# Cis_Honcho.net
KiCad netlist of a schematic drawn in EAGLE
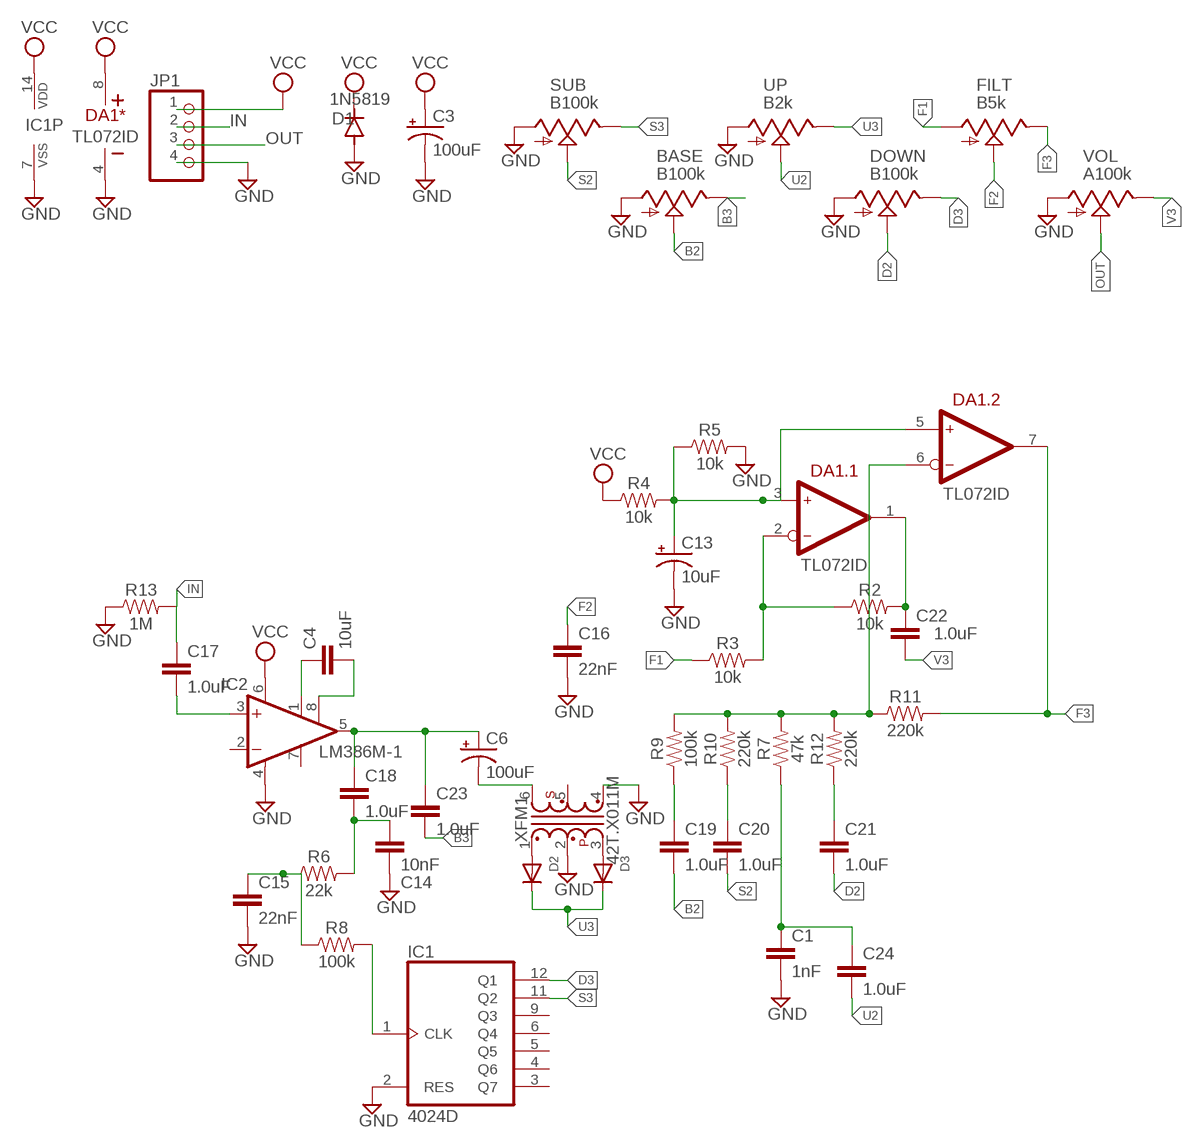
[diagram p0: schematic, sheet 1]

(export (version "E")
  (design (tool "Eeschema 10.0.6"))
  (components
    (comp (ref "BASE")
      (value "B100k")
      (footprint "eagle-import:9MM_SNAP-IN_POT")
      (libsource (lib "eagle-import") (part "9MM_SNAP-IN_POT_"))
    )
    (comp (ref "C1")
      (value "1nF")
      (footprint "eagle-import:0603")
      (libsource (lib "eagle-import") (part "1.0NF/1000PF-0603-50V-10%"))
    )
    (comp (ref "C3")
      (value "100uF")
      (footprint "eagle-import:E2,5-6")
      (libsource (lib "eagle-import") (part "CPOL-USE2.5-6"))
    )
    (comp (ref "C4")
      (value "10uF")
      (footprint "eagle-import:1210")
      (libsource (lib "eagle-import") (part "10UF-1210-50V-20%"))
    )
    (comp (ref "C6")
      (value "100uF")
      (footprint "eagle-import:E2,5-6")
      (libsource (lib "eagle-import") (part "CPOL-USE2.5-6"))
    )
    (comp (ref "C13")
      (value "10uF")
      (footprint "eagle-import:PANASONIC_B")
      (libsource (lib "eagle-import") (part "rcl_334_CPOL-USB"))
    )
    (comp (ref "C14")
      (value "10nF")
      (footprint "eagle-import:0603")
      (libsource (lib "eagle-import") (part "10NF-0603-50V-10%"))
    )
    (comp (ref "C15")
      (value "22nF")
      (footprint "eagle-import:0603")
      (libsource (lib "eagle-import") (part "22NF/22,000PF-0603-50V-10%"))
    )
    (comp (ref "C16")
      (value "22nF")
      (footprint "eagle-import:0603")
      (libsource (lib "eagle-import") (part "22NF/22,000PF-0603-50V-10%"))
    )
    (comp (ref "C17")
      (value "1.0uF")
      (footprint "eagle-import:0603")
      (libsource (lib "eagle-import") (part "1.0UF-0603-16V-10%"))
    )
    (comp (ref "C18")
      (value "1.0uF")
      (footprint "eagle-import:0603")
      (libsource (lib "eagle-import") (part "1.0UF-0603-16V-10%"))
    )
    (comp (ref "C19")
      (value "1.0uF")
      (footprint "eagle-import:0603")
      (libsource (lib "eagle-import") (part "1.0UF-0603-16V-10%"))
    )
    (comp (ref "C20")
      (value "1.0uF")
      (footprint "eagle-import:0603")
      (libsource (lib "eagle-import") (part "1.0UF-0603-16V-10%"))
    )
    (comp (ref "C21")
      (value "1.0uF")
      (footprint "eagle-import:0603")
      (libsource (lib "eagle-import") (part "1.0UF-0603-16V-10%"))
    )
    (comp (ref "C22")
      (value "1.0uF")
      (footprint "eagle-import:0603")
      (libsource (lib "eagle-import") (part "1.0UF-0603-16V-10%"))
    )
    (comp (ref "C23")
      (value "1.0uF")
      (footprint "eagle-import:0603")
      (libsource (lib "eagle-import") (part "1.0UF-0603-16V-10%"))
    )
    (comp (ref "C24")
      (value "1.0uF")
      (footprint "eagle-import:0603")
      (libsource (lib "eagle-import") (part "1.0UF-0603-16V-10%"))
    )
    (comp (ref "D1")
      (value "1N5819")
      (footprint "eagle-import:SOD123")
      (libsource (lib "eagle-import") (part "DIODE-SOD123"))
    )
    (comp (ref "D2")
      (value "DIODESOD-123")
      (footprint "eagle-import:SOD-123")
      (libsource (lib "eagle-import") (part "DIODESOD-123"))
    )
    (comp (ref "D3")
      (value "DIODESOD-123")
      (footprint "eagle-import:SOD-123")
      (libsource (lib "eagle-import") (part "DIODESOD-123"))
    )
    (comp (ref "DA1")
      (value "TL072ID")
      (footprint "eagle-import:SO-8")
      (libsource (lib "eagle-import") (part "TL072ID"))
    )
    (comp (ref "DOWN")
      (value "B100k")
      (footprint "eagle-import:9MM_SNAP-IN_POT")
      (libsource (lib "eagle-import") (part "9MM_SNAP-IN_POT_"))
    )
    (comp (ref "FILT")
      (value "B5k")
      (footprint "eagle-import:9MM_SNAP-IN_POT")
      (libsource (lib "eagle-import") (part "9MM_SNAP-IN_POT_"))
    )
    (comp (ref "IC1")
      (value "4024D")
      (footprint "eagle-import:SO14")
      (libsource (lib "eagle-import") (part "4024D"))
    )
    (comp (ref "IC2")
      (value "LM386M-1")
      (footprint "eagle-import:SO08")
      (libsource (lib "eagle-import") (part "LM386?-M1"))
    )
    (comp (ref "JP1")
      (value "PINHD-1X4")
      (footprint "eagle-import:1X04")
      (libsource (lib "eagle-import") (part "PINHD-1X4"))
    )
    (comp (ref "R2")
      (value "10k")
      (footprint "eagle-import:0603")
      (libsource (lib "eagle-import") (part "10KOHM-0603-1/10W-1%"))
    )
    (comp (ref "R3")
      (value "10k")
      (footprint "eagle-import:0603")
      (libsource (lib "eagle-import") (part "10KOHM-0603-1/10W-1%"))
    )
    (comp (ref "R4")
      (value "10k")
      (footprint "eagle-import:0603")
      (libsource (lib "eagle-import") (part "10KOHM-0603-1/10W-1%"))
    )
    (comp (ref "R5")
      (value "10k")
      (footprint "eagle-import:0603")
      (libsource (lib "eagle-import") (part "10KOHM-0603-1/10W-1%"))
    )
    (comp (ref "R6")
      (value "22k")
      (footprint "eagle-import:0603")
      (libsource (lib "eagle-import") (part "22KOHM-0603-1/10W-1%"))
    )
    (comp (ref "R7")
      (value "47k")
      (footprint "eagle-import:0603")
      (libsource (lib "eagle-import") (part "47KOHM-0603-1/10W-1%"))
    )
    (comp (ref "R8")
      (value "100k")
      (footprint "eagle-import:0603")
      (libsource (lib "eagle-import") (part "100KOHM-0603-1/10W-1%"))
    )
    (comp (ref "R9")
      (value "100k")
      (footprint "eagle-import:0603")
      (libsource (lib "eagle-import") (part "100KOHM-0603-1/10W-1%"))
    )
    (comp (ref "R10")
      (value "220k")
      (footprint "eagle-import:0603")
      (libsource (lib "eagle-import") (part "220KOHM-0603-1/10W-1%"))
    )
    (comp (ref "R11")
      (value "220k")
      (footprint "eagle-import:0603")
      (libsource (lib "eagle-import") (part "220KOHM-0603-1/10W-1%"))
    )
    (comp (ref "R12")
      (value "220k")
      (footprint "eagle-import:0603")
      (libsource (lib "eagle-import") (part "220KOHM-0603-1/10W-1%"))
    )
    (comp (ref "R13")
      (value "1M")
      (footprint "eagle-import:0603")
      (libsource (lib "eagle-import") (part "1MOHM-0603-1/4W-5%"))
    )
    (comp (ref "SUB")
      (value "B100k")
      (footprint "eagle-import:9MM_SNAP-IN_POT")
      (libsource (lib "eagle-import") (part "9MM_SNAP-IN_POT_"))
    )
    (comp (ref "UP")
      (value "B2k")
      (footprint "eagle-import:9MM_SNAP-IN_POT")
      (libsource (lib "eagle-import") (part "9MM_SNAP-IN_POT_"))
    )
    (comp (ref "VOL")
      (value "A100k")
      (footprint "eagle-import:9MM_SNAP-IN_POT")
      (libsource (lib "eagle-import") (part "9MM_SNAP-IN_POT_"))
    )
    (comp (ref "XFM1")
      (value "42T.X011M")
      (footprint "eagle-import:42TM")
      (libsource (lib "eagle-import") (part "42T.XM011"))
    )
  )
  (nets
    (net (code "1") (name "B2") (class "Default")
      (node (ref "BASE") (pin "2") (pinfunction "S_2") (pintype "passive"))
      (node (ref "C19") (pin "2") (pinfunction "2_2") (pintype "passive"))
    )
    (net (code "2") (name "B3") (class "Default")
      (node (ref "BASE") (pin "3") (pinfunction "E_3") (pintype "passive"))
      (node (ref "C23") (pin "2") (pinfunction "2_2") (pintype "passive"))
    )
    (net (code "3") (name "D2") (class "Default")
      (node (ref "C21") (pin "2") (pinfunction "2_2") (pintype "passive"))
      (node (ref "DOWN") (pin "2") (pinfunction "S_2") (pintype "passive"))
    )
    (net (code "4") (name "D3") (class "Default")
      (node (ref "DOWN") (pin "3") (pinfunction "E_3") (pintype "passive"))
      (node (ref "IC1") (pin "12") (pinfunction "Q1_12") (pintype "output"))
    )
    (net (code "5") (name "F1") (class "Default")
      (node (ref "FILT") (pin "1") (pinfunction "A_1") (pintype "passive"))
      (node (ref "R3") (pin "1") (pinfunction "1_1") (pintype "passive"))
    )
    (net (code "6") (name "F2") (class "Default")
      (node (ref "C16") (pin "1") (pinfunction "1_1") (pintype "passive"))
      (node (ref "FILT") (pin "2") (pinfunction "S_2") (pintype "passive"))
    )
    (net (code "7") (name "F3") (class "Default")
      (node (ref "DA1") (pin "7") (pinfunction "OUT_7") (pintype "output"))
      (node (ref "FILT") (pin "3") (pinfunction "E_3") (pintype "passive"))
      (node (ref "R11") (pin "2") (pinfunction "2_2") (pintype "passive"))
    )
    (net (code "8") (name "GND") (class "Default")
      (node (ref "BASE") (pin "1") (pinfunction "A_1") (pintype "passive"))
      (node (ref "C1") (pin "2") (pinfunction "2_2") (pintype "passive"))
      (node (ref "C13") (pin "-") (pinfunction "-_-") (pintype "passive"))
      (node (ref "C14") (pin "2") (pinfunction "2_2") (pintype "passive"))
      (node (ref "C15") (pin "2") (pinfunction "2_2") (pintype "passive"))
      (node (ref "C16") (pin "2") (pinfunction "2_2") (pintype "passive"))
      (node (ref "C3") (pin "-") (pinfunction "-_-") (pintype "passive"))
      (node (ref "D1") (pin "A") (pinfunction "A_A") (pintype "passive"))
      (node (ref "DA1") (pin "4") (pinfunction "V-_4") (pintype "power_in"))
      (node (ref "DOWN") (pin "1") (pinfunction "A_1") (pintype "passive"))
      (node (ref "IC1") (pin "2") (pinfunction "RES_2") (pintype "input"))
      (node (ref "IC1") (pin "7") (pinfunction "VSS_7") (pintype "power_in"))
      (node (ref "IC2") (pin "4") (pinfunction "GND_4") (pintype "power_in"))
      (node (ref "JP1") (pin "4") (pinfunction "4_4") (pintype "passive"))
      (node (ref "R13") (pin "1") (pinfunction "1_1") (pintype "passive"))
      (node (ref "R5") (pin "2") (pinfunction "2_2") (pintype "passive"))
      (node (ref "SUB") (pin "1") (pinfunction "A_1") (pintype "passive"))
      (node (ref "UP") (pin "1") (pinfunction "A_1") (pintype "passive"))
      (node (ref "VOL") (pin "1") (pinfunction "A_1") (pintype "passive"))
      (node (ref "XFM1") (pin "2") (pinfunction "2_2") (pintype "passive"))
      (node (ref "XFM1") (pin "4") (pinfunction "4_4") (pintype "passive"))
    )
    (net (code "9") (name "IN") (class "Default")
      (node (ref "C17") (pin "1") (pinfunction "1_1") (pintype "passive"))
      (node (ref "JP1") (pin "2") (pinfunction "2_2") (pintype "passive"))
      (node (ref "R13") (pin "2") (pinfunction "2_2") (pintype "passive"))
    )
    (net (code "10") (name "Net-(C1-Pad1)") (class "Default")
      (node (ref "C1") (pin "1") (pinfunction "1_1") (pintype "passive"))
      (node (ref "C24") (pin "1") (pinfunction "1_1") (pintype "passive"))
      (node (ref "R7") (pin "1") (pinfunction "1_1") (pintype "passive"))
    )
    (net (code "11") (name "Net-(C4-Pad1)") (class "Default")
      (node (ref "C4") (pin "1") (pinfunction "1_1") (pintype "passive"))
      (node (ref "IC2") (pin "1") (pinfunction "GAIN_1") (pintype "passive"))
    )
    (net (code "12") (name "Net-(C4-Pad2)") (class "Default")
      (node (ref "C4") (pin "2") (pinfunction "2_2") (pintype "passive"))
      (node (ref "IC2") (pin "8") (pinfunction "GAIN_8") (pintype "passive"))
    )
    (net (code "13") (name "Net-(C6-Pad-)") (class "Default")
      (node (ref "C6") (pin "-") (pinfunction "-_-") (pintype "passive"))
      (node (ref "XFM1") (pin "6") (pinfunction "6_6") (pintype "passive"))
    )
    (net (code "14") (name "Net-(C14-Pad1)") (class "Default")
      (node (ref "C14") (pin "1") (pinfunction "1_1") (pintype "passive"))
      (node (ref "C18") (pin "2") (pinfunction "2_2") (pintype "passive"))
      (node (ref "R6") (pin "2") (pinfunction "2_2") (pintype "passive"))
    )
    (net (code "15") (name "Net-(C15-Pad1)") (class "Default")
      (node (ref "C15") (pin "1") (pinfunction "1_1") (pintype "passive"))
      (node (ref "R6") (pin "1") (pinfunction "1_1") (pintype "passive"))
      (node (ref "R8") (pin "1") (pinfunction "1_1") (pintype "passive"))
    )
    (net (code "16") (name "Net-(C19-Pad1)") (class "Default")
      (node (ref "C19") (pin "1") (pinfunction "1_1") (pintype "passive"))
      (node (ref "R9") (pin "1") (pinfunction "1_1") (pintype "passive"))
    )
    (net (code "17") (name "Net-(C20-Pad1)") (class "Default")
      (node (ref "C20") (pin "1") (pinfunction "1_1") (pintype "passive"))
      (node (ref "R10") (pin "1") (pinfunction "1_1") (pintype "passive"))
    )
    (net (code "18") (name "Net-(C21-Pad1)") (class "Default")
      (node (ref "C21") (pin "1") (pinfunction "1_1") (pintype "passive"))
      (node (ref "R12") (pin "1") (pinfunction "1_1") (pintype "passive"))
    )
    (net (code "19") (name "Net-(D2-PadA)") (class "Default")
      (node (ref "D2") (pin "A") (pinfunction "A_A") (pintype "passive"))
      (node (ref "XFM1") (pin "1") (pinfunction "1_1") (pintype "passive"))
    )
    (net (code "20") (name "Net-(D3-PadA)") (class "Default")
      (node (ref "D3") (pin "A") (pinfunction "A_A") (pintype "passive"))
      (node (ref "XFM1") (pin "3") (pinfunction "3_3") (pintype "passive"))
    )
    (net (code "21") (name "Net-(DA1B-IN+)") (class "Default")
      (node (ref "C13") (pin "+") (pinfunction "+_+") (pintype "passive"))
      (node (ref "DA1") (pin "3") (pinfunction "IN+_3") (pintype "input"))
      (node (ref "DA1") (pin "5") (pinfunction "IN+_5") (pintype "input"))
      (node (ref "R4") (pin "2") (pinfunction "2_2") (pintype "passive"))
      (node (ref "R5") (pin "1") (pinfunction "1_1") (pintype "passive"))
    )
    (net (code "22") (name "Net-(DA1B-IN-)") (class "Default")
      (node (ref "DA1") (pin "2") (pinfunction "IN-_2") (pintype "input"))
      (node (ref "R2") (pin "1") (pinfunction "1_1") (pintype "passive"))
      (node (ref "R3") (pin "2") (pinfunction "2_2") (pintype "passive"))
    )
    (net (code "23") (name "Net-(DA1B-OUT)") (class "Default")
      (node (ref "C22") (pin "1") (pinfunction "1_1") (pintype "passive"))
      (node (ref "DA1") (pin "1") (pinfunction "OUT_1") (pintype "output"))
      (node (ref "R2") (pin "2") (pinfunction "2_2") (pintype "passive"))
    )
    (net (code "24") (name "Net-(DA1C-IN-)") (class "Default")
      (node (ref "DA1") (pin "6") (pinfunction "IN-_6") (pintype "input"))
      (node (ref "R10") (pin "2") (pinfunction "2_2") (pintype "passive"))
      (node (ref "R11") (pin "1") (pinfunction "1_1") (pintype "passive"))
      (node (ref "R12") (pin "2") (pinfunction "2_2") (pintype "passive"))
      (node (ref "R7") (pin "2") (pinfunction "2_2") (pintype "passive"))
      (node (ref "R9") (pin "2") (pinfunction "2_2") (pintype "passive"))
    )
    (net (code "25") (name "Net-(IC1A-CLK)") (class "Default")
      (node (ref "IC1") (pin "1") (pinfunction "CLK_1") (pintype "input"))
      (node (ref "R8") (pin "2") (pinfunction "2_2") (pintype "passive"))
    )
    (net (code "26") (name "Net-(IC2-+IN)") (class "Default")
      (node (ref "C17") (pin "2") (pinfunction "2_2") (pintype "passive"))
      (node (ref "IC2") (pin "3") (pinfunction "+IN_3") (pintype "input"))
    )
    (net (code "27") (name "Net-(IC2-OUT)") (class "Default")
      (node (ref "C18") (pin "1") (pinfunction "1_1") (pintype "passive"))
      (node (ref "C23") (pin "1") (pinfunction "1_1") (pintype "passive"))
      (node (ref "C6") (pin "+") (pinfunction "+_+") (pintype "passive"))
      (node (ref "IC2") (pin "5") (pinfunction "OUT_5") (pintype "output"))
    )
    (net (code "28") (name "OUT") (class "Default")
      (node (ref "JP1") (pin "3") (pinfunction "3_3") (pintype "passive"))
      (node (ref "VOL") (pin "2") (pinfunction "S_2") (pintype "passive"))
    )
    (net (code "29") (name "S2") (class "Default")
      (node (ref "C20") (pin "2") (pinfunction "2_2") (pintype "passive"))
      (node (ref "SUB") (pin "2") (pinfunction "S_2") (pintype "passive"))
    )
    (net (code "30") (name "S3") (class "Default")
      (node (ref "IC1") (pin "11") (pinfunction "Q2_11") (pintype "output"))
      (node (ref "SUB") (pin "3") (pinfunction "E_3") (pintype "passive"))
    )
    (net (code "31") (name "U2") (class "Default")
      (node (ref "C24") (pin "2") (pinfunction "2_2") (pintype "passive"))
      (node (ref "UP") (pin "2") (pinfunction "S_2") (pintype "passive"))
    )
    (net (code "32") (name "U3") (class "Default")
      (node (ref "D2") (pin "C") (pinfunction "C_C") (pintype "passive"))
      (node (ref "D3") (pin "C") (pinfunction "C_C") (pintype "passive"))
      (node (ref "UP") (pin "3") (pinfunction "E_3") (pintype "passive"))
    )
    (net (code "33") (name "V3") (class "Default")
      (node (ref "C22") (pin "2") (pinfunction "2_2") (pintype "passive"))
      (node (ref "VOL") (pin "3") (pinfunction "E_3") (pintype "passive"))
    )
    (net (code "34") (name "VCC") (class "Default")
      (node (ref "C3") (pin "+") (pinfunction "+_+") (pintype "passive"))
      (node (ref "D1") (pin "C") (pinfunction "C_C") (pintype "passive"))
      (node (ref "DA1") (pin "8") (pinfunction "V+_8") (pintype "power_in"))
      (node (ref "IC1") (pin "14") (pinfunction "VDD_14") (pintype "power_in"))
      (node (ref "IC2") (pin "6") (pinfunction "VS_6") (pintype "power_in"))
      (node (ref "JP1") (pin "1") (pinfunction "1_1") (pintype "passive"))
      (node (ref "R4") (pin "1") (pinfunction "1_1") (pintype "passive"))
    )
    (net (code "35") (name "unconnected-(IC1A-Q3-Pad9)") (class "Default")
      (node (ref "IC1") (pin "9") (pinfunction "Q3_9") (pintype "output"))
    )
    (net (code "36") (name "unconnected-(IC1A-Q4-Pad6)") (class "Default")
      (node (ref "IC1") (pin "6") (pinfunction "Q4_6") (pintype "output"))
    )
    (net (code "37") (name "unconnected-(IC1A-Q5-Pad5)") (class "Default")
      (node (ref "IC1") (pin "5") (pinfunction "Q5_5") (pintype "output"))
    )
    (net (code "38") (name "unconnected-(IC1A-Q6-Pad4)") (class "Default")
      (node (ref "IC1") (pin "4") (pinfunction "Q6_4") (pintype "output"))
    )
    (net (code "39") (name "unconnected-(IC1A-Q7-Pad3)") (class "Default")
      (node (ref "IC1") (pin "3") (pinfunction "Q7_3") (pintype "output"))
    )
    (net (code "40") (name "unconnected-(IC2--IN-Pad2)") (class "Default")
      (node (ref "IC2") (pin "2") (pinfunction "-IN_2") (pintype "input"))
    )
    (net (code "41") (name "unconnected-(IC2-BYPASS-Pad7)") (class "Default")
      (node (ref "IC2") (pin "7") (pinfunction "BYPASS_7") (pintype "passive"))
    )
    (net (code "42") (name "unconnected-(XFM1-Pad5)") (class "Default")
      (node (ref "XFM1") (pin "5") (pinfunction "5_5") (pintype "passive"))
    )
  )
)
